# ir02.net
KiCad netlist of a schematic drawn in EAGLE
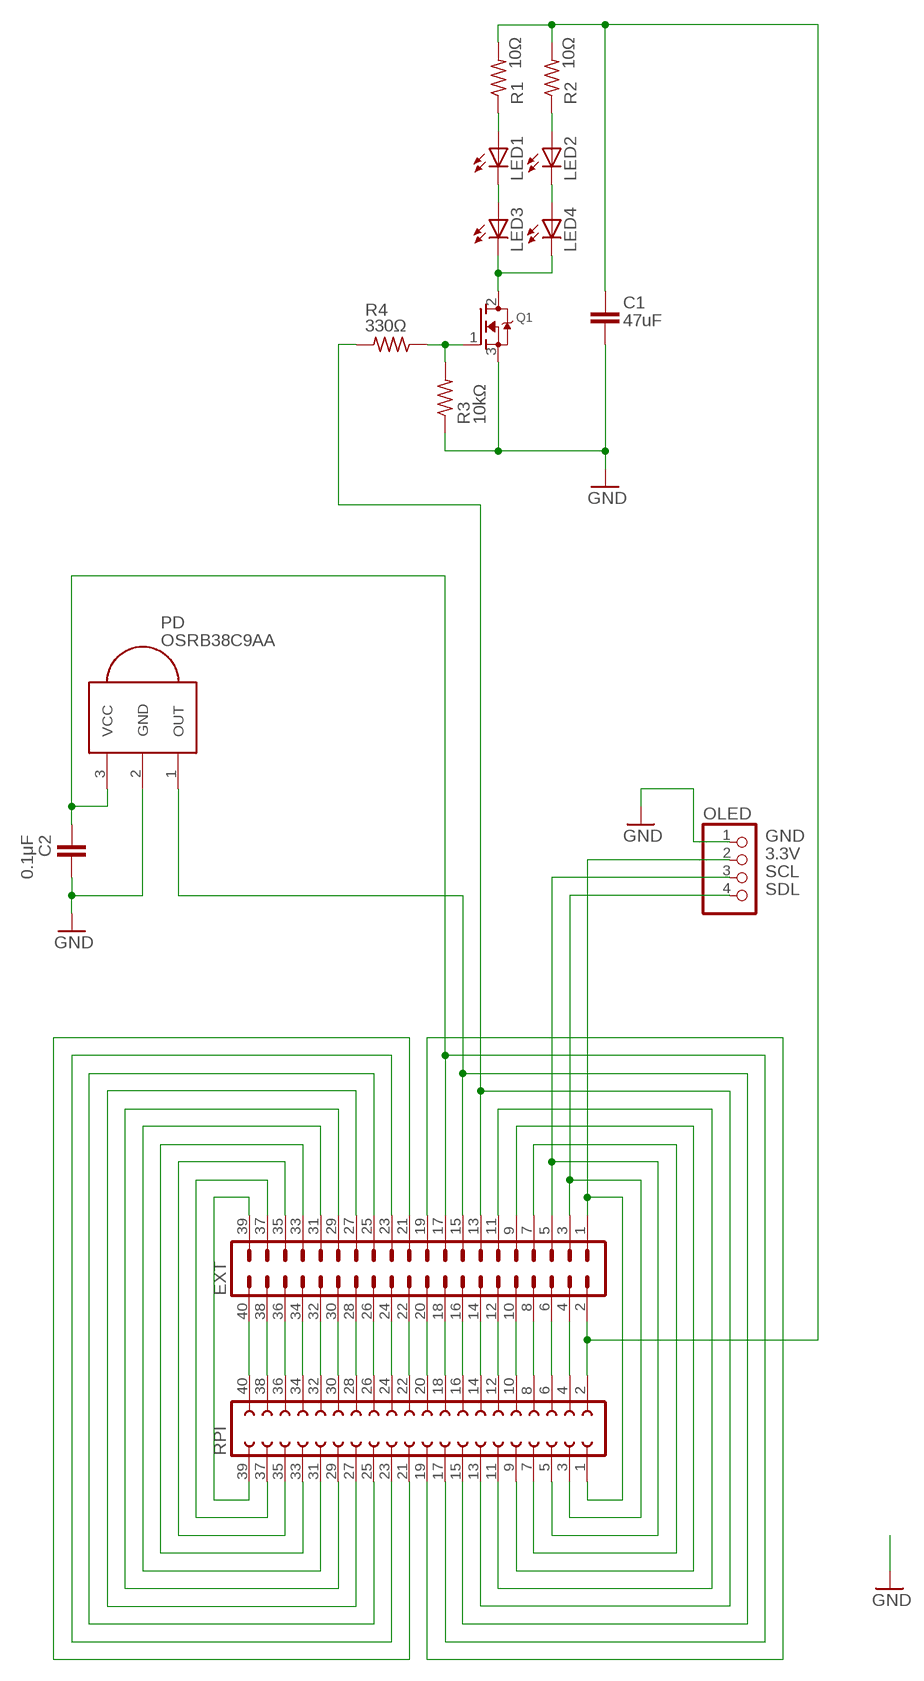
[diagram p0: schematic, sheet 1]

(export (version "E")
  (design (tool "Eeschema 10.0.6"))
  (components
    (comp (ref "C1")
      (value "47uF")
      (footprint "eagle-import:C025-025X050")
      (libsource (lib "eagle-import") (part "C-EU025-025X050"))
    )
    (comp (ref "C2")
      (value "0.1μF")
      (footprint "eagle-import:C025-025X050")
      (libsource (lib "eagle-import") (part "C-EU025-025X050"))
    )
    (comp (ref "EXT")
      (value "MA20-2")
      (footprint "eagle-import:MA20-2")
      (libsource (lib "eagle-import") (part "MA20-2"))
    )
    (comp (ref "LED1")
      (value "LED3MM")
      (footprint "eagle-import:LED3MM")
      (libsource (lib "eagle-import") (part "LED3MM"))
    )
    (comp (ref "LED2")
      (value "LED3MM")
      (footprint "eagle-import:LED3MM")
      (libsource (lib "eagle-import") (part "LED3MM"))
    )
    (comp (ref "LED3")
      (value "LED3MM")
      (footprint "eagle-import:LED3MM")
      (libsource (lib "eagle-import") (part "LED3MM"))
    )
    (comp (ref "LED4")
      (value "LED3MM")
      (footprint "eagle-import:LED3MM")
      (libsource (lib "eagle-import") (part "LED3MM"))
    )
    (comp (ref "OLED")
      (value "PINHD-1X4")
      (footprint "eagle-import:1X04")
      (libsource (lib "eagle-import") (part "PINHD-1X4"))
    )
    (comp (ref "PD")
      (value "OSRB38C9AA")
      (footprint "eagle-import:PNA460XM")
      (libsource (lib "eagle-import") (part "PNA460XM"))
    )
    (comp (ref "Q1")
      (value "MOSFET-NGDS_TO220V")
      (footprint "eagle-import:TO220V")
      (libsource (lib "eagle-import") (part "MOSFET-NGDS_TO220V"))
    )
    (comp (ref "R1")
      (value "10Ω")
      (footprint "eagle-import:0204_5")
      (libsource (lib "eagle-import") (part "R-US_0204/5"))
    )
    (comp (ref "R2")
      (value "10Ω")
      (footprint "eagle-import:0204_5")
      (libsource (lib "eagle-import") (part "R-US_0204/5"))
    )
    (comp (ref "R3")
      (value "10kΩ")
      (footprint "eagle-import:0204_5")
      (libsource (lib "eagle-import") (part "R-US_0204/5"))
    )
    (comp (ref "R4")
      (value "330Ω")
      (footprint "eagle-import:0204_5")
      (libsource (lib "eagle-import") (part "R-US_0204/5"))
    )
    (comp (ref "RPI")
      (value "FE20-2")
      (footprint "eagle-import:FE20-2")
      (libsource (lib "eagle-import") (part "FE20-2"))
    )
  )
  (nets
    (net (code "1") (name "/3.3V") (class "Default")
      (node (ref "C2") (pin "1") (pinfunction "1_1") (pintype "passive"))
      (node (ref "EXT") (pin "1") (pinfunction "1_1") (pintype "passive"))
      (node (ref "EXT") (pin "17") (pinfunction "17_17") (pintype "passive"))
      (node (ref "OLED") (pin "2") (pinfunction "2_2") (pintype "passive"))
      (node (ref "PD") (pin "3") (pinfunction "VCC_3") (pintype "power_in"))
      (node (ref "RPI") (pin "1") (pinfunction "1_1") (pintype "passive"))
      (node (ref "RPI") (pin "17") (pinfunction "17_17") (pintype "passive"))
    )
    (net (code "2") (name "/SCL") (class "Default")
      (node (ref "EXT") (pin "5") (pinfunction "5_5") (pintype "passive"))
      (node (ref "OLED") (pin "3") (pinfunction "3_3") (pintype "passive"))
      (node (ref "RPI") (pin "5") (pinfunction "5_5") (pintype "passive"))
    )
    (net (code "3") (name "/SDL") (class "Default")
      (node (ref "EXT") (pin "3") (pinfunction "3_3") (pintype "passive"))
      (node (ref "OLED") (pin "4") (pinfunction "4_4") (pintype "passive"))
      (node (ref "RPI") (pin "3") (pinfunction "3_3") (pintype "passive"))
    )
    (net (code "4") (name "GND") (class "Default")
      (node (ref "C1") (pin "2") (pinfunction "2_2") (pintype "passive"))
      (node (ref "C2") (pin "2") (pinfunction "2_2") (pintype "passive"))
      (node (ref "EXT") (pin "14") (pinfunction "14_14") (pintype "passive"))
      (node (ref "EXT") (pin "34") (pinfunction "34_34") (pintype "passive"))
      (node (ref "EXT") (pin "39") (pinfunction "39_39") (pintype "passive"))
      (node (ref "EXT") (pin "6") (pinfunction "6_6") (pintype "passive"))
      (node (ref "EXT") (pin "9") (pinfunction "9_9") (pintype "passive"))
      (node (ref "OLED") (pin "1") (pinfunction "1_1") (pintype "passive"))
      (node (ref "PD") (pin "2") (pinfunction "GND_2") (pintype "power_in"))
      (node (ref "Q1") (pin "3") (pinfunction "S_3") (pintype "bidirectional"))
      (node (ref "R3") (pin "1") (pinfunction "1_1") (pintype "passive"))
      (node (ref "RPI") (pin "14") (pinfunction "14_14") (pintype "passive"))
      (node (ref "RPI") (pin "34") (pinfunction "34_34") (pintype "passive"))
      (node (ref "RPI") (pin "39") (pinfunction "39_39") (pintype "passive"))
      (node (ref "RPI") (pin "6") (pinfunction "6_6") (pintype "passive"))
      (node (ref "RPI") (pin "9") (pinfunction "9_9") (pintype "passive"))
    )
    (net (code "5") (name "Net-(C1-Pad1)") (class "Default")
      (node (ref "C1") (pin "1") (pinfunction "1_1") (pintype "passive"))
      (node (ref "EXT") (pin "2") (pinfunction "2_2") (pintype "passive"))
      (node (ref "R1") (pin "2") (pinfunction "2_2") (pintype "passive"))
      (node (ref "R2") (pin "2") (pinfunction "2_2") (pintype "passive"))
      (node (ref "RPI") (pin "2") (pinfunction "2_2") (pintype "passive"))
    )
    (net (code "6") (name "Net-(EXT-Pad4)") (class "Default")
      (node (ref "EXT") (pin "4") (pinfunction "4_4") (pintype "passive"))
      (node (ref "RPI") (pin "4") (pinfunction "4_4") (pintype "passive"))
    )
    (net (code "7") (name "Net-(EXT-Pad7)") (class "Default")
      (node (ref "EXT") (pin "7") (pinfunction "7_7") (pintype "passive"))
      (node (ref "RPI") (pin "7") (pinfunction "7_7") (pintype "passive"))
    )
    (net (code "8") (name "Net-(EXT-Pad8)") (class "Default")
      (node (ref "EXT") (pin "8") (pinfunction "8_8") (pintype "passive"))
      (node (ref "RPI") (pin "8") (pinfunction "8_8") (pintype "passive"))
    )
    (net (code "9") (name "Net-(EXT-Pad10)") (class "Default")
      (node (ref "EXT") (pin "10") (pinfunction "10_10") (pintype "passive"))
      (node (ref "RPI") (pin "10") (pinfunction "10_10") (pintype "passive"))
    )
    (net (code "10") (name "Net-(EXT-Pad11)") (class "Default")
      (node (ref "EXT") (pin "11") (pinfunction "11_11") (pintype "passive"))
      (node (ref "RPI") (pin "11") (pinfunction "11_11") (pintype "passive"))
    )
    (net (code "11") (name "Net-(EXT-Pad12)") (class "Default")
      (node (ref "EXT") (pin "12") (pinfunction "12_12") (pintype "passive"))
      (node (ref "RPI") (pin "12") (pinfunction "12_12") (pintype "passive"))
    )
    (net (code "12") (name "Net-(EXT-Pad13)") (class "Default")
      (node (ref "EXT") (pin "13") (pinfunction "13_13") (pintype "passive"))
      (node (ref "R4") (pin "2") (pinfunction "2_2") (pintype "passive"))
      (node (ref "RPI") (pin "13") (pinfunction "13_13") (pintype "passive"))
    )
    (net (code "13") (name "Net-(EXT-Pad16)") (class "Default")
      (node (ref "EXT") (pin "16") (pinfunction "16_16") (pintype "passive"))
      (node (ref "RPI") (pin "16") (pinfunction "16_16") (pintype "passive"))
    )
    (net (code "14") (name "Net-(EXT-Pad18)") (class "Default")
      (node (ref "EXT") (pin "18") (pinfunction "18_18") (pintype "passive"))
      (node (ref "RPI") (pin "18") (pinfunction "18_18") (pintype "passive"))
    )
    (net (code "15") (name "Net-(EXT-Pad19)") (class "Default")
      (node (ref "EXT") (pin "19") (pinfunction "19_19") (pintype "passive"))
      (node (ref "RPI") (pin "19") (pinfunction "19_19") (pintype "passive"))
    )
    (net (code "16") (name "Net-(EXT-Pad20)") (class "Default")
      (node (ref "EXT") (pin "20") (pinfunction "20_20") (pintype "passive"))
      (node (ref "RPI") (pin "20") (pinfunction "20_20") (pintype "passive"))
    )
    (net (code "17") (name "Net-(EXT-Pad21)") (class "Default")
      (node (ref "EXT") (pin "21") (pinfunction "21_21") (pintype "passive"))
      (node (ref "RPI") (pin "21") (pinfunction "21_21") (pintype "passive"))
    )
    (net (code "18") (name "Net-(EXT-Pad22)") (class "Default")
      (node (ref "EXT") (pin "22") (pinfunction "22_22") (pintype "passive"))
      (node (ref "RPI") (pin "22") (pinfunction "22_22") (pintype "passive"))
    )
    (net (code "19") (name "Net-(EXT-Pad23)") (class "Default")
      (node (ref "EXT") (pin "23") (pinfunction "23_23") (pintype "passive"))
      (node (ref "RPI") (pin "23") (pinfunction "23_23") (pintype "passive"))
    )
    (net (code "20") (name "Net-(EXT-Pad24)") (class "Default")
      (node (ref "EXT") (pin "24") (pinfunction "24_24") (pintype "passive"))
      (node (ref "RPI") (pin "24") (pinfunction "24_24") (pintype "passive"))
    )
    (net (code "21") (name "Net-(EXT-Pad25)") (class "Default")
      (node (ref "EXT") (pin "25") (pinfunction "25_25") (pintype "passive"))
      (node (ref "RPI") (pin "25") (pinfunction "25_25") (pintype "passive"))
    )
    (net (code "22") (name "Net-(EXT-Pad26)") (class "Default")
      (node (ref "EXT") (pin "26") (pinfunction "26_26") (pintype "passive"))
      (node (ref "RPI") (pin "26") (pinfunction "26_26") (pintype "passive"))
    )
    (net (code "23") (name "Net-(EXT-Pad27)") (class "Default")
      (node (ref "EXT") (pin "27") (pinfunction "27_27") (pintype "passive"))
      (node (ref "RPI") (pin "27") (pinfunction "27_27") (pintype "passive"))
    )
    (net (code "24") (name "Net-(EXT-Pad28)") (class "Default")
      (node (ref "EXT") (pin "28") (pinfunction "28_28") (pintype "passive"))
      (node (ref "RPI") (pin "28") (pinfunction "28_28") (pintype "passive"))
    )
    (net (code "25") (name "Net-(EXT-Pad29)") (class "Default")
      (node (ref "EXT") (pin "29") (pinfunction "29_29") (pintype "passive"))
      (node (ref "RPI") (pin "29") (pinfunction "29_29") (pintype "passive"))
    )
    (net (code "26") (name "Net-(EXT-Pad30)") (class "Default")
      (node (ref "EXT") (pin "30") (pinfunction "30_30") (pintype "passive"))
      (node (ref "RPI") (pin "30") (pinfunction "30_30") (pintype "passive"))
    )
    (net (code "27") (name "Net-(EXT-Pad31)") (class "Default")
      (node (ref "EXT") (pin "31") (pinfunction "31_31") (pintype "passive"))
      (node (ref "RPI") (pin "31") (pinfunction "31_31") (pintype "passive"))
    )
    (net (code "28") (name "Net-(EXT-Pad32)") (class "Default")
      (node (ref "EXT") (pin "32") (pinfunction "32_32") (pintype "passive"))
      (node (ref "RPI") (pin "32") (pinfunction "32_32") (pintype "passive"))
    )
    (net (code "29") (name "Net-(EXT-Pad33)") (class "Default")
      (node (ref "EXT") (pin "33") (pinfunction "33_33") (pintype "passive"))
      (node (ref "RPI") (pin "33") (pinfunction "33_33") (pintype "passive"))
    )
    (net (code "30") (name "Net-(EXT-Pad35)") (class "Default")
      (node (ref "EXT") (pin "35") (pinfunction "35_35") (pintype "passive"))
      (node (ref "RPI") (pin "35") (pinfunction "35_35") (pintype "passive"))
    )
    (net (code "31") (name "Net-(EXT-Pad36)") (class "Default")
      (node (ref "EXT") (pin "36") (pinfunction "36_36") (pintype "passive"))
      (node (ref "RPI") (pin "36") (pinfunction "36_36") (pintype "passive"))
    )
    (net (code "32") (name "Net-(EXT-Pad37)") (class "Default")
      (node (ref "EXT") (pin "37") (pinfunction "37_37") (pintype "passive"))
      (node (ref "RPI") (pin "37") (pinfunction "37_37") (pintype "passive"))
    )
    (net (code "33") (name "Net-(EXT-Pad38)") (class "Default")
      (node (ref "EXT") (pin "38") (pinfunction "38_38") (pintype "passive"))
      (node (ref "RPI") (pin "38") (pinfunction "38_38") (pintype "passive"))
    )
    (net (code "34") (name "Net-(EXT-Pad40)") (class "Default")
      (node (ref "EXT") (pin "40") (pinfunction "40_40") (pintype "passive"))
      (node (ref "RPI") (pin "40") (pinfunction "40_40") (pintype "passive"))
    )
    (net (code "35") (name "Net-(LED1-C)") (class "Default")
      (node (ref "LED1") (pin "K") (pinfunction "C_K") (pintype "passive"))
      (node (ref "LED3") (pin "A") (pinfunction "A_A") (pintype "passive"))
    )
    (net (code "36") (name "Net-(LED1-PadA)") (class "Default")
      (node (ref "LED1") (pin "A") (pinfunction "A_A") (pintype "passive"))
      (node (ref "R1") (pin "1") (pinfunction "1_1") (pintype "passive"))
    )
    (net (code "37") (name "Net-(LED2-C)") (class "Default")
      (node (ref "LED2") (pin "K") (pinfunction "C_K") (pintype "passive"))
      (node (ref "LED4") (pin "A") (pinfunction "A_A") (pintype "passive"))
    )
    (net (code "38") (name "Net-(LED2-PadA)") (class "Default")
      (node (ref "LED2") (pin "A") (pinfunction "A_A") (pintype "passive"))
      (node (ref "R2") (pin "1") (pinfunction "1_1") (pintype "passive"))
    )
    (net (code "39") (name "Net-(LED3-C)") (class "Default")
      (node (ref "LED3") (pin "K") (pinfunction "C_K") (pintype "passive"))
      (node (ref "LED4") (pin "K") (pinfunction "C_K") (pintype "passive"))
      (node (ref "Q1") (pin "2") (pinfunction "D_2") (pintype "bidirectional"))
    )
    (net (code "40") (name "Net-(PD-OUT)") (class "Default")
      (node (ref "EXT") (pin "15") (pinfunction "15_15") (pintype "passive"))
      (node (ref "PD") (pin "1") (pinfunction "OUT_1") (pintype "output"))
      (node (ref "RPI") (pin "15") (pinfunction "15_15") (pintype "passive"))
    )
    (net (code "41") (name "Net-(Q1-G)") (class "Default")
      (node (ref "Q1") (pin "1") (pinfunction "G_1") (pintype "bidirectional"))
      (node (ref "R3") (pin "2") (pinfunction "2_2") (pintype "passive"))
      (node (ref "R4") (pin "1") (pinfunction "1_1") (pintype "passive"))
    )
  )
)
